# ArbPwrBoost_P8.net
KiCad netlist of a schematic drawn in Altium Designer
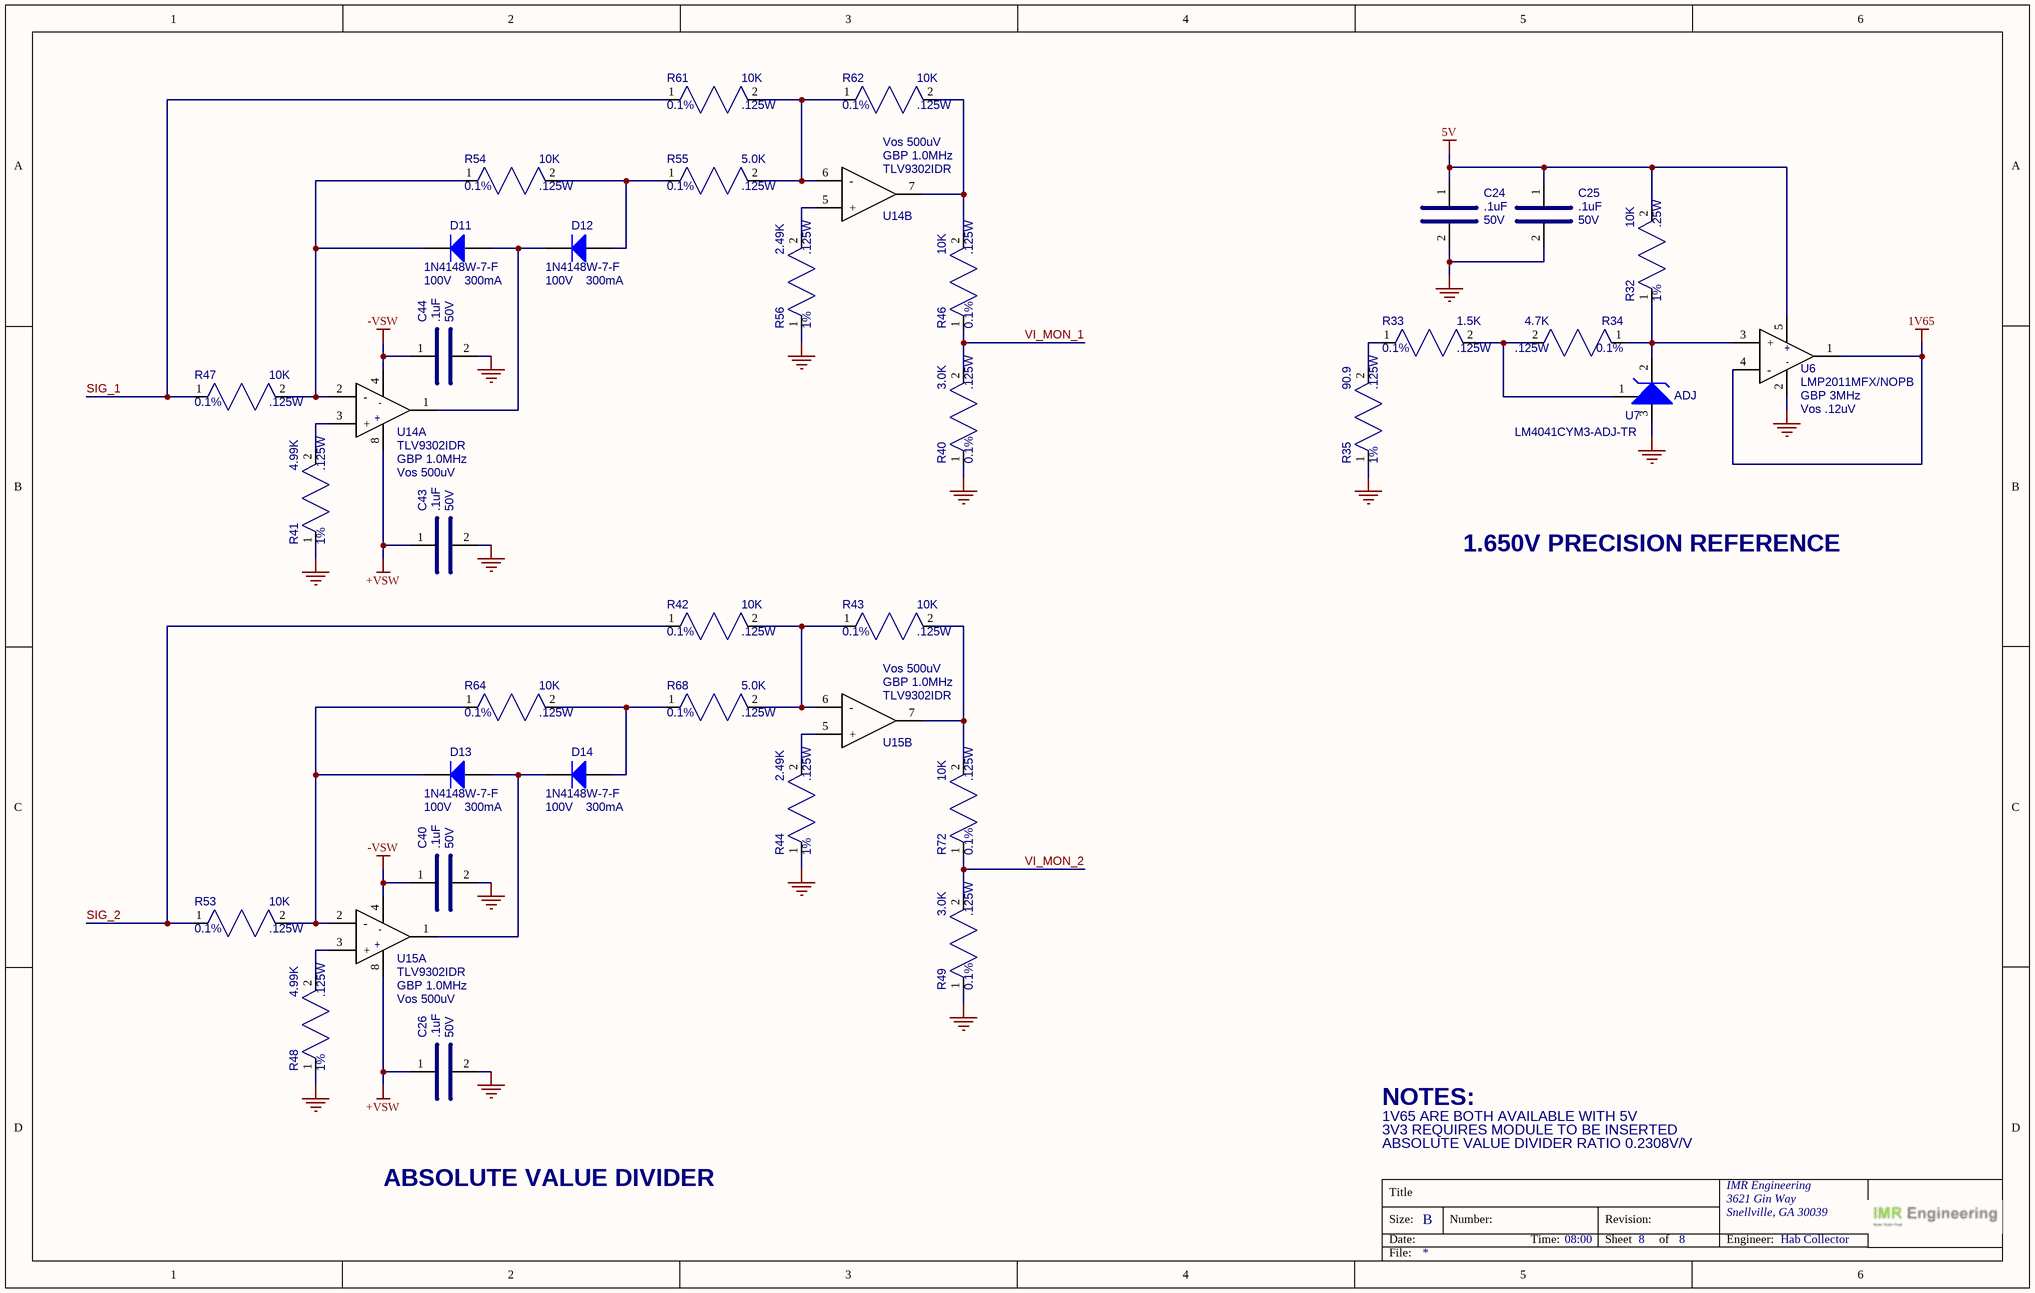
[diagram p0: ArbPwrBoost_P8.SchDoc]

(export (version "E")
  (design (tool "Eeschema 10.0.6"))
  (components
    (comp (ref "C24")
      (value ".1uF")
      (footprint "CAP_0805")
      (description "CAP CER 0.1UF 50V X7R 0805")
      (fields
        (field (name "MFG") "KYOCERA AVX")
        (field (name "VOLTAGE") "50V")
        (field (name "Comment") "KGM21NR71H104KT")
      )
      (libsource (lib "IMR_LIB_SCH_R2") (part "CAP_SMD_0.1UF_50V_0805"))
    )
    (comp (ref "C25")
      (value ".1uF")
      (footprint "CAP_0805")
      (description "CAP CER 0.1UF 50V X7R 0805")
      (fields
        (field (name "MFG") "KYOCERA AVX")
        (field (name "VOLTAGE") "50V")
        (field (name "Comment") "KGM21NR71H104KT")
      )
      (libsource (lib "IMR_LIB_SCH_R2") (part "CAP_SMD_0.1UF_50V_0805"))
    )
    (comp (ref "C26")
      (value ".1uF")
      (footprint "CAP_0805")
      (description "CAP CER 0.1UF 50V X7R 0805")
      (fields
        (field (name "MFG") "KYOCERA AVX")
        (field (name "VOLTAGE") "50V")
        (field (name "Comment") "KGM21NR71H104KT")
      )
      (libsource (lib "IMR_LIB_SCH_R2") (part "CAP_SMD_0.1UF_50V_0805"))
    )
    (comp (ref "C40")
      (value ".1uF")
      (footprint "CAP_0805")
      (description "CAP CER 0.1UF 50V X7R 0805")
      (fields
        (field (name "MFG") "KYOCERA AVX")
        (field (name "VOLTAGE") "50V")
        (field (name "Comment") "KGM21NR71H104KT")
      )
      (libsource (lib "IMR_LIB_SCH_R2") (part "CAP_SMD_0.1UF_50V_0805"))
    )
    (comp (ref "C43")
      (value ".1uF")
      (footprint "CAP_0805")
      (description "CAP CER 0.1UF 50V X7R 0805")
      (fields
        (field (name "MFG") "KYOCERA AVX")
        (field (name "VOLTAGE") "50V")
        (field (name "Comment") "KGM21NR71H104KT")
      )
      (libsource (lib "IMR_LIB_SCH_R2") (part "CAP_SMD_0.1UF_50V_0805"))
    )
    (comp (ref "C44")
      (value ".1uF")
      (footprint "CAP_0805")
      (description "CAP CER 0.1UF 50V X7R 0805")
      (fields
        (field (name "MFG") "KYOCERA AVX")
        (field (name "VOLTAGE") "50V")
        (field (name "Comment") "KGM21NR71H104KT")
      )
      (libsource (lib "IMR_LIB_SCH_R2") (part "CAP_SMD_0.1UF_50V_0805"))
    )
    (comp (ref "D11")
      (value "100V")
      (footprint "SOD123")
      (description "RELAY REED SPDT 250MA 5V")
      (fields
        (field (name "MFG") "Diodes Inc")
        (field (name "MFG_PN") "1N4148W-7-F")
        (field (name "CURRENT") "300mA")
        (field (name "Comment") "1N4148W-7-F")
      )
      (libsource (lib "IMR_LIB_SCH_R2") (part "DIODE_1N4148W-7-F"))
    )
    (comp (ref "D12")
      (value "100V")
      (footprint "SOD123")
      (description "RELAY REED SPDT 250MA 5V")
      (fields
        (field (name "MFG") "Diodes Inc")
        (field (name "MFG_PN") "1N4148W-7-F")
        (field (name "CURRENT") "300mA")
        (field (name "Comment") "1N4148W-7-F")
      )
      (libsource (lib "IMR_LIB_SCH_R2") (part "DIODE_1N4148W-7-F"))
    )
    (comp (ref "D13")
      (value "100V")
      (footprint "SOD123")
      (description "RELAY REED SPDT 250MA 5V")
      (fields
        (field (name "MFG") "Diodes Inc")
        (field (name "MFG_PN") "1N4148W-7-F")
        (field (name "CURRENT") "300mA")
        (field (name "Comment") "1N4148W-7-F")
      )
      (libsource (lib "IMR_LIB_SCH_R2") (part "DIODE_1N4148W-7-F"))
    )
    (comp (ref "D14")
      (value "100V")
      (footprint "SOD123")
      (description "RELAY REED SPDT 250MA 5V")
      (fields
        (field (name "MFG") "Diodes Inc")
        (field (name "MFG_PN") "1N4148W-7-F")
        (field (name "CURRENT") "300mA")
        (field (name "Comment") "1N4148W-7-F")
      )
      (libsource (lib "IMR_LIB_SCH_R2") (part "DIODE_1N4148W-7-F"))
    )
    (comp (ref "R32")
      (value "10K")
      (footprint "RES_0805")
      (description "RES SMD 10K OHM 1% 1/4W 0805")
      (fields
        (field (name "MFG") "Yageo")
        (field (name "POWER") ".25W")
        (field (name "TOLERANCE") "1%")
        (field (name "Comment") "RC0805FR-7W10KL")
      )
      (libsource (lib "IMR_LIB_SCH_R2") (part "RES_SMD_10K_0805_1/4W_1%"))
    )
    (comp (ref "R33")
      (value "1.5K")
      (footprint "RES_0805")
      (description "RES SMD 1.5K OHM 0.1% 1/8W 0805")
      (fields
        (field (name "MFG") "Yageo")
        (field (name "POWER") ".125W")
        (field (name "TOLERANCE") "0.1%")
        (field (name "Comment") "RT0805BRD071K5L")
      )
      (libsource (lib "IMR_LIB_SCH_R2") (part "RES_SMD_1.5K_0805_1/8W_0.1%"))
    )
    (comp (ref "R34")
      (value "4.7K")
      (footprint "RES_0805")
      (description "RES SMD 4.7K OHM 0.1% 1/8W 0805")
      (fields
        (field (name "MFG") "Yageo")
        (field (name "POWER") ".125W")
        (field (name "TOLERANCE") "0.1%")
        (field (name "Comment") "RT0805BRD074K7L")
      )
      (libsource (lib "IMR_LIB_SCH_R2") (part "RES_SMD_4.7K_0805_1/8W_0.1%"))
    )
    (comp (ref "R35")
      (value "90.9")
      (footprint "RES_0805")
      (description "RES SMD 90.9 OHM 1% 1/8W 0805")
      (fields
        (field (name "MFG") "Yageo")
        (field (name "POWER") ".125W")
        (field (name "TOLERANCE") "1%")
        (field (name "Comment") "RC0805FR-0790R9L")
      )
      (libsource (lib "IMR_LIB_SCH_R2") (part "RES_SMD_90.9_0805_1/8W_1%"))
    )
    (comp (ref "R40")
      (value "3.0K")
      (footprint "RES_0805")
      (description "RES SMD 3.0K OHM 0.1% 1/8W 0805")
      (fields
        (field (name "MFG") "Yageo")
        (field (name "POWER") ".125W")
        (field (name "TOLERANCE") "0.1%")
        (field (name "Comment") "RT0805BRD073KL")
      )
      (libsource (lib "IMR_LIB_SCH_R2") (part "RES_SMD_3.0K_0805_1/8W_0.1%"))
    )
    (comp (ref "R41")
      (value "4.99K")
      (footprint "RES_0805")
      (description "RES SMD 4.99K OHM 1% 1/8W 0805")
      (fields
        (field (name "MFG") "Yageo")
        (field (name "POWER") ".125W")
        (field (name "TOLERANCE") "1%")
        (field (name "Comment") "RC0805FR-134K99L")
      )
      (libsource (lib "IMR_LIB_SCH_R2") (part "RES_SMD_4.99K_0805_1/8W_1%"))
    )
    (comp (ref "R42")
      (value "10K")
      (footprint "RES_0805")
      (description "RES SMD 10K OHM 0.1% 1/8W 0805")
      (fields
        (field (name "MFG") "Yageo")
        (field (name "POWER") ".125W")
        (field (name "TOLERANCE") "0.1%")
        (field (name "Comment") "RP0805BRD0710KL")
      )
      (libsource (lib "IMR_LIB_SCH_R2") (part "RES_SMD_10K_0805_1/8W_0.1%"))
    )
    (comp (ref "R43")
      (value "10K")
      (footprint "RES_0805")
      (description "RES SMD 10K OHM 0.1% 1/8W 0805")
      (fields
        (field (name "MFG") "Yageo")
        (field (name "POWER") ".125W")
        (field (name "TOLERANCE") "0.1%")
        (field (name "Comment") "RP0805BRD0710KL")
      )
      (libsource (lib "IMR_LIB_SCH_R2") (part "RES_SMD_10K_0805_1/8W_0.1%"))
    )
    (comp (ref "R44")
      (value "2.49K")
      (footprint "RES_0805")
      (description "RES SMD 2.49K OHM 1% 1/8W 0805")
      (fields
        (field (name "MFG") "Yageo")
        (field (name "POWER") ".125W")
        (field (name "TOLERANCE") "1%")
        (field (name "Comment") "RC0805FR-132K49L")
      )
      (libsource (lib "IMR_LIB_SCH_R2") (part "RES_SMD_2.49K_0805_1/8W_1%"))
    )
    (comp (ref "R46")
      (value "10K")
      (footprint "RES_0805")
      (description "RES SMD 10K OHM 0.1% 1/8W 0805")
      (fields
        (field (name "MFG") "Yageo")
        (field (name "POWER") ".125W")
        (field (name "TOLERANCE") "0.1%")
        (field (name "Comment") "RP0805BRD0710KL")
      )
      (libsource (lib "IMR_LIB_SCH_R2") (part "RES_SMD_10K_0805_1/8W_0.1%"))
    )
    (comp (ref "R47")
      (value "10K")
      (footprint "RES_0805")
      (description "RES SMD 10K OHM 0.1% 1/8W 0805")
      (fields
        (field (name "MFG") "Yageo")
        (field (name "POWER") ".125W")
        (field (name "TOLERANCE") "0.1%")
        (field (name "Comment") "RP0805BRD0710KL")
      )
      (libsource (lib "IMR_LIB_SCH_R2") (part "RES_SMD_10K_0805_1/8W_0.1%"))
    )
    (comp (ref "R48")
      (value "4.99K")
      (footprint "RES_0805")
      (description "RES SMD 4.99K OHM 1% 1/8W 0805")
      (fields
        (field (name "MFG") "Yageo")
        (field (name "POWER") ".125W")
        (field (name "TOLERANCE") "1%")
        (field (name "Comment") "RC0805FR-134K99L")
      )
      (libsource (lib "IMR_LIB_SCH_R2") (part "RES_SMD_4.99K_0805_1/8W_1%"))
    )
    (comp (ref "R49")
      (value "3.0K")
      (footprint "RES_0805")
      (description "RES SMD 3.0K OHM 0.1% 1/8W 0805")
      (fields
        (field (name "MFG") "Yageo")
        (field (name "POWER") ".125W")
        (field (name "TOLERANCE") "0.1%")
        (field (name "Comment") "RT0805BRD073KL")
      )
      (libsource (lib "IMR_LIB_SCH_R2") (part "RES_SMD_3.0K_0805_1/8W_0.1%"))
    )
    (comp (ref "R53")
      (value "10K")
      (footprint "RES_0805")
      (description "RES SMD 10K OHM 0.1% 1/8W 0805")
      (fields
        (field (name "MFG") "Yageo")
        (field (name "POWER") ".125W")
        (field (name "TOLERANCE") "0.1%")
        (field (name "Comment") "RP0805BRD0710KL")
      )
      (libsource (lib "IMR_LIB_SCH_R2") (part "RES_SMD_10K_0805_1/8W_0.1%"))
    )
    (comp (ref "R54")
      (value "10K")
      (footprint "RES_0805")
      (description "RES SMD 10K OHM 0.1% 1/8W 0805")
      (fields
        (field (name "MFG") "Yageo")
        (field (name "POWER") ".125W")
        (field (name "TOLERANCE") "0.1%")
        (field (name "Comment") "RP0805BRD0710KL")
      )
      (libsource (lib "IMR_LIB_SCH_R2") (part "RES_SMD_10K_0805_1/8W_0.1%"))
    )
    (comp (ref "R55")
      (value "5.0K")
      (footprint "RES_0805")
      (description "RES SMD 5.0K OHM 0.1% 1/8W 0805")
      (fields
        (field (name "MFG") "Yageo")
        (field (name "POWER") ".125W")
        (field (name "TOLERANCE") "0.1%")
        (field (name "Comment") "AT0805BRD075KL")
      )
      (libsource (lib "IMR_LIB_SCH_R2") (part "RES_SMD_5.0K_0805_1/8W_0.1%"))
    )
    (comp (ref "R56")
      (value "2.49K")
      (footprint "RES_0805")
      (description "RES SMD 2.49K OHM 1% 1/8W 0805")
      (fields
        (field (name "MFG") "Yageo")
        (field (name "POWER") ".125W")
        (field (name "TOLERANCE") "1%")
        (field (name "Comment") "RC0805FR-132K49L")
      )
      (libsource (lib "IMR_LIB_SCH_R2") (part "RES_SMD_2.49K_0805_1/8W_1%"))
    )
    (comp (ref "R61")
      (value "10K")
      (footprint "RES_0805")
      (description "RES SMD 10K OHM 0.1% 1/8W 0805")
      (fields
        (field (name "MFG") "Yageo")
        (field (name "POWER") ".125W")
        (field (name "TOLERANCE") "0.1%")
        (field (name "Comment") "RP0805BRD0710KL")
      )
      (libsource (lib "IMR_LIB_SCH_R2") (part "RES_SMD_10K_0805_1/8W_0.1%"))
    )
    (comp (ref "R62")
      (value "10K")
      (footprint "RES_0805")
      (description "RES SMD 10K OHM 0.1% 1/8W 0805")
      (fields
        (field (name "MFG") "Yageo")
        (field (name "POWER") ".125W")
        (field (name "TOLERANCE") "0.1%")
        (field (name "Comment") "RP0805BRD0710KL")
      )
      (libsource (lib "IMR_LIB_SCH_R2") (part "RES_SMD_10K_0805_1/8W_0.1%"))
    )
    (comp (ref "R64")
      (value "10K")
      (footprint "RES_0805")
      (description "RES SMD 10K OHM 0.1% 1/8W 0805")
      (fields
        (field (name "MFG") "Yageo")
        (field (name "POWER") ".125W")
        (field (name "TOLERANCE") "0.1%")
        (field (name "Comment") "RP0805BRD0710KL")
      )
      (libsource (lib "IMR_LIB_SCH_R2") (part "RES_SMD_10K_0805_1/8W_0.1%"))
    )
    (comp (ref "R68")
      (value "5.0K")
      (footprint "RES_0805")
      (description "RES SMD 5.0K OHM 0.1% 1/8W 0805")
      (fields
        (field (name "MFG") "Yageo")
        (field (name "POWER") ".125W")
        (field (name "TOLERANCE") "0.1%")
        (field (name "Comment") "AT0805BRD075KL")
      )
      (libsource (lib "IMR_LIB_SCH_R2") (part "RES_SMD_5.0K_0805_1/8W_0.1%"))
    )
    (comp (ref "R72")
      (value "10K")
      (footprint "RES_0805")
      (description "RES SMD 10K OHM 0.1% 1/8W 0805")
      (fields
        (field (name "MFG") "Yageo")
        (field (name "POWER") ".125W")
        (field (name "TOLERANCE") "0.1%")
        (field (name "Comment") "RP0805BRD0710KL")
      )
      (libsource (lib "IMR_LIB_SCH_R2") (part "RES_SMD_10K_0805_1/8W_0.1%"))
    )
    (comp (ref "U6")
      (value "GBP 3MHz")
      (footprint "SOT-23-5")
      (description "IC OPAMP GP 3MHZ .12uV CIRCUIT SOT23-5")
      (fields
        (field (name "MFG") "Texas Instruments")
        (field (name "MFG_PN") "LMP2011MFX/NOPB")
        (field (name "VOS") "Vos .12uV")
        (field (name "Comment") "LMP2011MFX/NOPB")
      )
      (libsource (lib "IMR_LIB_SCH_R2") (part "OPAMP_LMP2011MFX/NOPB"))
    )
    (comp (ref "U7")
      (value "ADJ")
      (footprint "SOT-23")
      (description "IC VREF SHUNT ADJ 0.5% SOT23-3")
      (fields
        (field (name "MFG") "Microchip")
        (field (name "MFG_PN") "LM4041CYM3-ADJ-TR")
        (field (name "Comment") "LM4041CYM3-ADJ-TR")
      )
      (libsource (lib "IMR_LIB_SCH_R2") (part "IC_LM4041CYM3-ADJ-TR"))
    )
    (comp (ref "U14")
      (value "GBP 1.0MHz")
      (footprint "SOIC-8_49")
      (description "IC OPAMP GP 2 CIRCUIT 8SOIC")
      (fields
        (field (name "MFG") "Texas Instruments")
        (field (name "MFG_PN") "TLV9302IDR")
        (field (name "VOS") "Vos 500uV")
        (field (name "Comment") "TLV9302IDR")
      )
      (libsource (lib "IMR_LIB_SCH_R2") (part "OPAMP_TLV9302IDR"))
    )
    (comp (ref "U15")
      (value "GBP 1.0MHz")
      (footprint "SOIC-8_49")
      (description "IC OPAMP GP 2 CIRCUIT 8SOIC")
      (fields
        (field (name "MFG") "Texas Instruments")
        (field (name "MFG_PN") "TLV9302IDR")
        (field (name "VOS") "Vos 500uV")
        (field (name "Comment") "TLV9302IDR")
      )
      (libsource (lib "IMR_LIB_SCH_R2") (part "OPAMP_TLV9302IDR"))
    )
  )
  (nets
    (net (code "1") (name "+VSW") (class "Default")
      (node (ref "C26") (pin "1") (pinfunction "1_1") (pintype "passive"))
      (node (ref "C43") (pin "1") (pinfunction "1_1") (pintype "passive"))
      (node (ref "U14") (pin "8") (pintype "passive"))
      (node (ref "U15") (pin "8") (pintype "passive"))
    )
    (net (code "2") (name "-VSW") (class "Default")
      (node (ref "C40") (pin "1") (pinfunction "1_1") (pintype "passive"))
      (node (ref "C44") (pin "1") (pinfunction "1_1") (pintype "passive"))
      (node (ref "U14") (pin "4") (pintype "passive"))
      (node (ref "U15") (pin "4") (pintype "passive"))
    )
    (net (code "3") (name "/SIG_1") (class "Default")
      (node (ref "R47") (pin "1") (pinfunction "1_1") (pintype "passive"))
      (node (ref "R61") (pin "1") (pinfunction "1_1") (pintype "passive"))
    )
    (net (code "4") (name "/SIG_2") (class "Default")
      (node (ref "R42") (pin "1") (pinfunction "1_1") (pintype "passive"))
      (node (ref "R53") (pin "1") (pinfunction "1_1") (pintype "passive"))
    )
    (net (code "5") (name "/VI_MON_1") (class "Default")
      (node (ref "R40") (pin "2") (pinfunction "2_2") (pintype "passive"))
      (node (ref "R46") (pin "1") (pinfunction "1_1") (pintype "passive"))
    )
    (net (code "6") (name "/VI_MON_2") (class "Default")
      (node (ref "R49") (pin "2") (pinfunction "2_2") (pintype "passive"))
      (node (ref "R72") (pin "1") (pinfunction "1_1") (pintype "passive"))
    )
    (net (code "7") (name "1V65") (class "Default")
      (node (ref "U6") (pin "1") (pintype "passive"))
      (node (ref "U6") (pin "4") (pinfunction "-_4") (pintype "passive"))
    )
    (net (code "8") (name "5V") (class "Default")
      (node (ref "C24") (pin "1") (pinfunction "1_1") (pintype "passive"))
      (node (ref "C25") (pin "1") (pinfunction "1_1") (pintype "passive"))
      (node (ref "R32") (pin "2") (pinfunction "2_2") (pintype "passive"))
      (node (ref "U6") (pin "5") (pintype "passive"))
    )
    (net (code "9") (name "GND") (class "Default")
      (node (ref "C24") (pin "2") (pinfunction "2_2") (pintype "passive"))
      (node (ref "C25") (pin "2") (pinfunction "2_2") (pintype "passive"))
      (node (ref "C26") (pin "2") (pinfunction "2_2") (pintype "passive"))
      (node (ref "C40") (pin "2") (pinfunction "2_2") (pintype "passive"))
      (node (ref "C43") (pin "2") (pinfunction "2_2") (pintype "passive"))
      (node (ref "C44") (pin "2") (pinfunction "2_2") (pintype "passive"))
      (node (ref "R35") (pin "1") (pinfunction "1_1") (pintype "passive"))
      (node (ref "R40") (pin "1") (pinfunction "1_1") (pintype "passive"))
      (node (ref "R41") (pin "1") (pinfunction "1_1") (pintype "passive"))
      (node (ref "R44") (pin "1") (pinfunction "1_1") (pintype "passive"))
      (node (ref "R48") (pin "1") (pinfunction "1_1") (pintype "passive"))
      (node (ref "R49") (pin "1") (pinfunction "1_1") (pintype "passive"))
      (node (ref "R56") (pin "1") (pinfunction "1_1") (pintype "passive"))
      (node (ref "U6") (pin "2") (pintype "passive"))
      (node (ref "U7") (pin "3") (pinfunction "A_3") (pintype "passive"))
    )
    (net (code "10") (name "Net-(D11-A)") (class "Default")
      (node (ref "D11") (pin "1") (pinfunction "A_1") (pintype "passive"))
      (node (ref "D12") (pin "2") (pinfunction "K_2") (pintype "passive"))
      (node (ref "U14") (pin "1") (pintype "passive"))
    )
    (net (code "11") (name "Net-(D11-K)") (class "Default")
      (node (ref "D11") (pin "2") (pinfunction "K_2") (pintype "passive"))
      (node (ref "R47") (pin "2") (pinfunction "2_2") (pintype "passive"))
      (node (ref "R54") (pin "1") (pinfunction "1_1") (pintype "passive"))
      (node (ref "U14") (pin "2") (pinfunction "-_2") (pintype "passive"))
    )
    (net (code "12") (name "Net-(D12-A)") (class "Default")
      (node (ref "D12") (pin "1") (pinfunction "A_1") (pintype "passive"))
      (node (ref "R54") (pin "2") (pinfunction "2_2") (pintype "passive"))
      (node (ref "R55") (pin "1") (pinfunction "1_1") (pintype "passive"))
    )
    (net (code "13") (name "Net-(D13-A)") (class "Default")
      (node (ref "D13") (pin "1") (pinfunction "A_1") (pintype "passive"))
      (node (ref "D14") (pin "2") (pinfunction "K_2") (pintype "passive"))
      (node (ref "U15") (pin "1") (pintype "passive"))
    )
    (net (code "14") (name "Net-(D13-K)") (class "Default")
      (node (ref "D13") (pin "2") (pinfunction "K_2") (pintype "passive"))
      (node (ref "R53") (pin "2") (pinfunction "2_2") (pintype "passive"))
      (node (ref "R64") (pin "1") (pinfunction "1_1") (pintype "passive"))
      (node (ref "U15") (pin "2") (pinfunction "-_2") (pintype "passive"))
    )
    (net (code "15") (name "Net-(D14-A)") (class "Default")
      (node (ref "D14") (pin "1") (pinfunction "A_1") (pintype "passive"))
      (node (ref "R64") (pin "2") (pinfunction "2_2") (pintype "passive"))
      (node (ref "R68") (pin "1") (pinfunction "1_1") (pintype "passive"))
    )
    (net (code "16") (name "Net-(R33-Pad1)") (class "Default")
      (node (ref "R33") (pin "1") (pinfunction "1_1") (pintype "passive"))
      (node (ref "R35") (pin "2") (pinfunction "2_2") (pintype "passive"))
    )
    (net (code "17") (name "Net-(R43-Pad2)") (class "Default")
      (node (ref "R43") (pin "2") (pinfunction "2_2") (pintype "passive"))
      (node (ref "R72") (pin "2") (pinfunction "2_2") (pintype "passive"))
      (node (ref "U15") (pin "7") (pintype "passive"))
    )
    (net (code "18") (name "Net-(R46-Pad2)") (class "Default")
      (node (ref "R46") (pin "2") (pinfunction "2_2") (pintype "passive"))
      (node (ref "R62") (pin "2") (pinfunction "2_2") (pintype "passive"))
      (node (ref "U14") (pin "7") (pintype "passive"))
    )
    (net (code "19") (name "Net-(U6-+)") (class "Default")
      (node (ref "R32") (pin "1") (pinfunction "1_1") (pintype "passive"))
      (node (ref "R34") (pin "1") (pinfunction "1_1") (pintype "passive"))
      (node (ref "U6") (pin "3") (pinfunction "+_3") (pintype "passive"))
      (node (ref "U7") (pin "2") (pinfunction "K_2") (pintype "passive"))
    )
    (net (code "20") (name "Net-(U7-FB)") (class "Default")
      (node (ref "R33") (pin "2") (pinfunction "2_2") (pintype "passive"))
      (node (ref "R34") (pin "2") (pinfunction "2_2") (pintype "passive"))
      (node (ref "U7") (pin "1") (pinfunction "FB_1") (pintype "passive"))
    )
    (net (code "21") (name "Net-(U14A-+)") (class "Default")
      (node (ref "R41") (pin "2") (pinfunction "2_2") (pintype "passive"))
      (node (ref "U14") (pin "3") (pinfunction "+_3") (pintype "passive"))
    )
    (net (code "22") (name "Net-(U14B-+)") (class "Default")
      (node (ref "R56") (pin "2") (pinfunction "2_2") (pintype "passive"))
      (node (ref "U14") (pin "5") (pinfunction "+_5") (pintype "passive"))
    )
    (net (code "23") (name "Net-(U14B--)") (class "Default")
      (node (ref "R55") (pin "2") (pinfunction "2_2") (pintype "passive"))
      (node (ref "R61") (pin "2") (pinfunction "2_2") (pintype "passive"))
      (node (ref "R62") (pin "1") (pinfunction "1_1") (pintype "passive"))
      (node (ref "U14") (pin "6") (pinfunction "-_6") (pintype "passive"))
    )
    (net (code "24") (name "Net-(U15A-+)") (class "Default")
      (node (ref "R48") (pin "2") (pinfunction "2_2") (pintype "passive"))
      (node (ref "U15") (pin "3") (pinfunction "+_3") (pintype "passive"))
    )
    (net (code "25") (name "Net-(U15B-+)") (class "Default")
      (node (ref "R44") (pin "2") (pinfunction "2_2") (pintype "passive"))
      (node (ref "U15") (pin "5") (pinfunction "+_5") (pintype "passive"))
    )
    (net (code "26") (name "Net-(U15B--)") (class "Default")
      (node (ref "R42") (pin "2") (pinfunction "2_2") (pintype "passive"))
      (node (ref "R43") (pin "1") (pinfunction "1_1") (pintype "passive"))
      (node (ref "R68") (pin "2") (pinfunction "2_2") (pintype "passive"))
      (node (ref "U15") (pin "6") (pinfunction "-_6") (pintype "passive"))
    )
  )
)
